# 328_data_collector.net
KiCad netlist of a schematic drawn in EAGLE
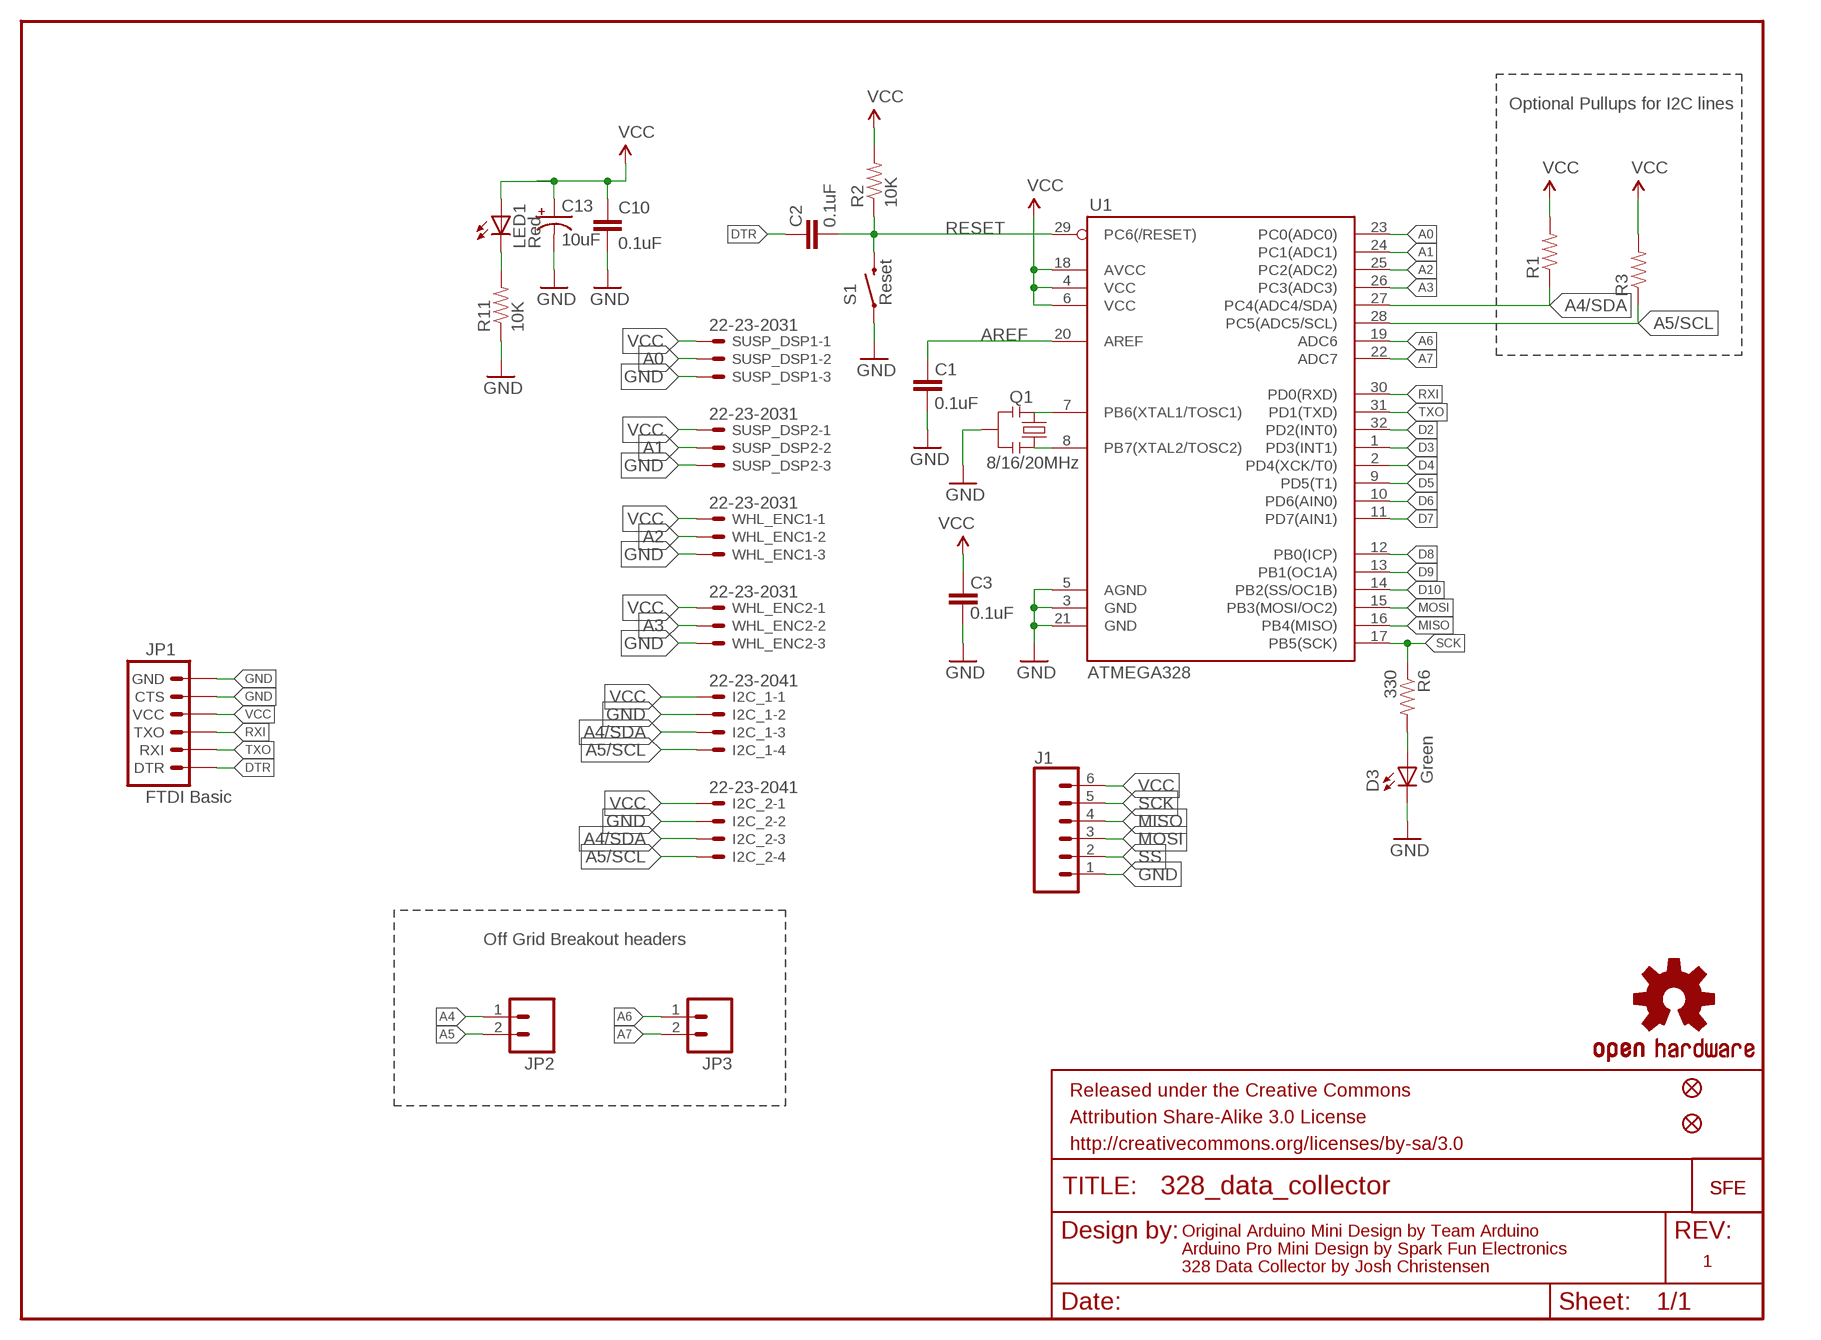
[diagram p0: schematic, sheet 1]

(export (version "E")
  (design (tool "Eeschema 10.0.6"))
  (components
    (comp (ref "C1")
      (value "0.1uF")
      (footprint "eagle-import:0603-CAP")
      (libsource (lib "eagle-import") (part "CAP0603-CAP"))
    )
    (comp (ref "C2")
      (value "0.1uF")
      (footprint "eagle-import:0603-CAP")
      (libsource (lib "eagle-import") (part "CAP0603-CAP"))
    )
    (comp (ref "C3")
      (value "0.1uF")
      (footprint "eagle-import:0603-CAP")
      (libsource (lib "eagle-import") (part "CAP0603-CAP"))
    )
    (comp (ref "C10")
      (value "0.1uF")
      (footprint "eagle-import:0603-CAP")
      (libsource (lib "eagle-import") (part "CAP0603-CAP"))
    )
    (comp (ref "C13")
      (value "10uF")
      (footprint "eagle-import:EIA3216")
      (libsource (lib "eagle-import") (part "CAP_POL1206"))
    )
    (comp (ref "D3")
      (value "Green")
      (footprint "eagle-import:0603-LED-ALT1")
      (libsource (lib "eagle-import") (part "LED"))
    )
    (comp (ref "FRAME1")
      (value "FRAME-LETTER")
      (footprint "eagle-import:CREATIVE_COMMONS")
      (libsource (lib "eagle-import") (part "FRAME-LETTER"))
    )
    (comp (ref "I2C_1")
      (value "22-23-2041")
      (footprint "eagle-import:22-23-2041")
      (fields (field (name "MF") "MOLEX"))
      (libsource (lib "eagle-import") (part "22-23-2041"))
    )
    (comp (ref "I2C_2")
      (value "22-23-2041")
      (footprint "eagle-import:22-23-2041")
      (fields (field (name "MF") "MOLEX"))
      (libsource (lib "eagle-import") (part "22-23-2041"))
    )
    (comp (ref "J1")
      (value "CONN_06SILK_FEMALE_PTH")
      (footprint "eagle-import:1X06")
      (libsource (lib "eagle-import") (part "CONN_06SILK_FEMALE_PTH"))
    )
    (comp (ref "JP1")
      (value "FTDI Basic")
      (footprint "eagle-import:1X06")
      (libsource (lib "eagle-import") (part "ARDUINO_SERIAL_PROGRAMPTH"))
    )
    (comp (ref "JP2")
      (value "M02PTH")
      (footprint "eagle-import:1X02")
      (libsource (lib "eagle-import") (part "M02PTH"))
    )
    (comp (ref "JP3")
      (value "M02PTH")
      (footprint "eagle-import:1X02")
      (libsource (lib "eagle-import") (part "M02PTH"))
    )
    (comp (ref "JP5")
      (value "FIDUCIALUFIDUCIAL")
      (footprint "eagle-import:MICRO-FIDUCIAL")
      (libsource (lib "eagle-import") (part "FIDUCIALUFIDUCIAL"))
    )
    (comp (ref "JP8")
      (value "FIDUCIALUFIDUCIAL")
      (footprint "eagle-import:MICRO-FIDUCIAL")
      (libsource (lib "eagle-import") (part "FIDUCIALUFIDUCIAL"))
    )
    (comp (ref "LED1")
      (value "Red")
      (footprint "eagle-import:0603-LED-ALT1")
      (libsource (lib "eagle-import") (part "LED"))
    )
    (comp (ref "Q1")
      (value "8/16/20MHz")
      (footprint "eagle-import:RESONATOR-SMD-1_1")
      (libsource (lib "eagle-import") (part "RESONATOR1{colon}1"))
    )
    (comp (ref "R1")
      (value "RESISTOR0603-RES")
      (footprint "eagle-import:0603-RES")
      (libsource (lib "eagle-import") (part "RESISTOR0603-RES"))
    )
    (comp (ref "R2")
      (value "10K")
      (footprint "eagle-import:0603-RES")
      (libsource (lib "eagle-import") (part "RESISTOR0603-RES"))
    )
    (comp (ref "R3")
      (value "RESISTOR0603-RES")
      (footprint "eagle-import:0603-RES")
      (libsource (lib "eagle-import") (part "RESISTOR0603-RES"))
    )
    (comp (ref "R6")
      (value "330")
      (footprint "eagle-import:0603-RES")
      (libsource (lib "eagle-import") (part "RESISTOR0603-RES"))
    )
    (comp (ref "R11")
      (value "10K")
      (footprint "eagle-import:0603-RES")
      (libsource (lib "eagle-import") (part "RESISTOR0603-RES"))
    )
    (comp (ref "S1")
      (value "Reset")
      (footprint "eagle-import:TACTILE-SWITCH-SMD-ALT01")
      (libsource (lib "eagle-import") (part "SWITCH-MOMENTARY-2SMD-ALT01"))
    )
    (comp (ref "SUSP_DSP1")
      (value "22-23-2031")
      (footprint "eagle-import:22-23-2031")
      (fields (field (name "MF") "MOLEX"))
      (libsource (lib "eagle-import") (part "22-23-2031"))
    )
    (comp (ref "SUSP_DSP2")
      (value "22-23-2031")
      (footprint "eagle-import:22-23-2031")
      (fields (field (name "MF") "MOLEX"))
      (libsource (lib "eagle-import") (part "22-23-2031"))
    )
    (comp (ref "U$1")
      (value "LOGO-SFESK")
      (footprint "eagle-import:SFE-LOGO-FLAME")
      (libsource (lib "eagle-import") (part "LOGO-SFESK"))
    )
    (comp (ref "U$3")
      (value "OSHW-LOGOS")
      (footprint "eagle-import:OSHW-LOGO-S")
      (libsource (lib "eagle-import") (part "OSHW-LOGOS"))
    )
    (comp (ref "U$11")
      (value "LOGO-SFENEW")
      (footprint "eagle-import:SFE-NEW-WEBLOGO")
      (libsource (lib "eagle-import") (part "LOGO-SFENEW"))
    )
    (comp (ref "U1")
      (value "ATMEGA328")
      (footprint "eagle-import:TQFP32-08")
      (libsource (lib "eagle-import") (part "ATMEGA168"))
    )
    (comp (ref "WHL_ENC1")
      (value "22-23-2031")
      (footprint "eagle-import:22-23-2031")
      (fields (field (name "MF") "MOLEX"))
      (libsource (lib "eagle-import") (part "22-23-2031"))
    )
    (comp (ref "WHL_ENC2")
      (value "22-23-2031")
      (footprint "eagle-import:22-23-2031")
      (fields (field (name "MF") "MOLEX"))
      (libsource (lib "eagle-import") (part "22-23-2031"))
    )
  )
  (nets
    (net (code "1") (name "/AREF") (class "Default")
      (node (ref "C1") (pin "2") (pinfunction "2_2") (pintype "passive"))
      (node (ref "U1") (pin "20") (pinfunction "AREF_20") (pintype "bidirectional"))
    )
    (net (code "2") (name "/RESET") (class "Default")
      (node (ref "C2") (pin "1") (pinfunction "1_1") (pintype "passive"))
      (node (ref "R2") (pin "1") (pinfunction "1_1") (pintype "passive"))
      (node (ref "S1") (pin "3") (pinfunction "2_3") (pintype "passive"))
      (node (ref "S1") (pin "4") (pinfunction "2_4") (pintype "passive"))
      (node (ref "U1") (pin "29") (pinfunction "PC6(/RESET)_29") (pintype "bidirectional"))
    )
    (net (code "3") (name "A0") (class "Default")
      (node (ref "SUSP_DSP1") (pin "2") (pinfunction "S_2") (pintype "passive"))
      (node (ref "U1") (pin "23") (pinfunction "PC0(ADC0)_23") (pintype "bidirectional"))
    )
    (net (code "4") (name "A1") (class "Default")
      (node (ref "SUSP_DSP2") (pin "2") (pinfunction "S_2") (pintype "passive"))
      (node (ref "U1") (pin "24") (pinfunction "PC1(ADC1)_24") (pintype "bidirectional"))
    )
    (net (code "5") (name "A2") (class "Default")
      (node (ref "U1") (pin "25") (pinfunction "PC2(ADC2)_25") (pintype "bidirectional"))
      (node (ref "WHL_ENC1") (pin "2") (pinfunction "S_2") (pintype "passive"))
    )
    (net (code "6") (name "A3") (class "Default")
      (node (ref "U1") (pin "26") (pinfunction "PC3(ADC3)_26") (pintype "bidirectional"))
      (node (ref "WHL_ENC2") (pin "2") (pinfunction "S_2") (pintype "passive"))
    )
    (net (code "7") (name "A4") (class "Default")
      (node (ref "JP2") (pin "1") (pinfunction "1_1") (pintype "passive"))
    )
    (net (code "8") (name "A4{slash}SDA") (class "Default")
      (node (ref "I2C_1") (pin "3") (pinfunction "S_3") (pintype "passive"))
      (node (ref "I2C_2") (pin "3") (pinfunction "S_3") (pintype "passive"))
      (node (ref "R1") (pin "1") (pinfunction "1_1") (pintype "passive"))
      (node (ref "U1") (pin "27") (pinfunction "PC4(ADC4/SDA)_27") (pintype "bidirectional"))
    )
    (net (code "9") (name "A5") (class "Default")
      (node (ref "JP2") (pin "2") (pinfunction "2_2") (pintype "passive"))
    )
    (net (code "10") (name "A5{slash}SCL") (class "Default")
      (node (ref "I2C_1") (pin "4") (pinfunction "S_4") (pintype "passive"))
      (node (ref "I2C_2") (pin "4") (pinfunction "S_4") (pintype "passive"))
      (node (ref "R3") (pin "1") (pinfunction "1_1") (pintype "passive"))
      (node (ref "U1") (pin "28") (pinfunction "PC5(ADC5/SCL)_28") (pintype "bidirectional"))
    )
    (net (code "11") (name "A6") (class "Default")
      (node (ref "JP3") (pin "1") (pinfunction "1_1") (pintype "passive"))
      (node (ref "U1") (pin "19") (pinfunction "ADC6_19") (pintype "bidirectional"))
    )
    (net (code "12") (name "A7") (class "Default")
      (node (ref "JP3") (pin "2") (pinfunction "2_2") (pintype "passive"))
      (node (ref "U1") (pin "22") (pinfunction "ADC7_22") (pintype "bidirectional"))
    )
    (net (code "13") (name "D2") (class "Default")
      (node (ref "U1") (pin "32") (pinfunction "PD2(INT0)_32") (pintype "bidirectional"))
    )
    (net (code "14") (name "D3") (class "Default")
      (node (ref "U1") (pin "1") (pinfunction "PD3(INT1)_1") (pintype "bidirectional"))
    )
    (net (code "15") (name "D4") (class "Default")
      (node (ref "U1") (pin "2") (pinfunction "PD4(XCK/T0)_2") (pintype "bidirectional"))
    )
    (net (code "16") (name "D5") (class "Default")
      (node (ref "U1") (pin "9") (pinfunction "PD5(T1)_9") (pintype "bidirectional"))
    )
    (net (code "17") (name "D6") (class "Default")
      (node (ref "U1") (pin "10") (pinfunction "PD6(AIN0)_10") (pintype "bidirectional"))
    )
    (net (code "18") (name "D7") (class "Default")
      (node (ref "U1") (pin "11") (pinfunction "PD7(AIN1)_11") (pintype "bidirectional"))
    )
    (net (code "19") (name "D8") (class "Default")
      (node (ref "U1") (pin "12") (pinfunction "PB0(ICP)_12") (pintype "bidirectional"))
    )
    (net (code "20") (name "D9") (class "Default")
      (node (ref "U1") (pin "13") (pinfunction "PB1(OC1A)_13") (pintype "bidirectional"))
    )
    (net (code "21") (name "D10") (class "Default")
      (node (ref "U1") (pin "14") (pinfunction "PB2(SS/OC1B)_14") (pintype "bidirectional"))
    )
    (net (code "22") (name "DTR") (class "Default")
      (node (ref "C2") (pin "2") (pinfunction "2_2") (pintype "passive"))
      (node (ref "JP1") (pin "1") (pinfunction "DTR_1") (pintype "passive"))
    )
    (net (code "23") (name "GND") (class "Default")
      (node (ref "C1") (pin "1") (pinfunction "1_1") (pintype "passive"))
      (node (ref "C10") (pin "2") (pinfunction "2_2") (pintype "passive"))
      (node (ref "C13") (pin "C") (pinfunction "-_C") (pintype "passive"))
      (node (ref "C3") (pin "1") (pinfunction "1_1") (pintype "passive"))
      (node (ref "D3") (pin "C") (pinfunction "C_C") (pintype "passive"))
      (node (ref "I2C_1") (pin "2") (pinfunction "S_2") (pintype "passive"))
      (node (ref "I2C_2") (pin "2") (pinfunction "S_2") (pintype "passive"))
      (node (ref "J1") (pin "1") (pinfunction "1_1") (pintype "passive"))
      (node (ref "JP1") (pin "5") (pinfunction "CTS_5") (pintype "passive"))
      (node (ref "JP1") (pin "6") (pinfunction "GND_6") (pintype "passive"))
      (node (ref "Q1") (pin "2") (pinfunction "2_2") (pintype "passive"))
      (node (ref "R11") (pin "1") (pinfunction "1_1") (pintype "passive"))
      (node (ref "S1") (pin "1") (pinfunction "1_1") (pintype "passive"))
      (node (ref "S1") (pin "2") (pinfunction "1_2") (pintype "passive"))
      (node (ref "SUSP_DSP1") (pin "3") (pinfunction "S_3") (pintype "passive"))
      (node (ref "SUSP_DSP2") (pin "3") (pinfunction "S_3") (pintype "passive"))
      (node (ref "U1") (pin "21") (pinfunction "GND_21") (pintype "bidirectional"))
      (node (ref "U1") (pin "3") (pinfunction "GND_3") (pintype "bidirectional"))
      (node (ref "U1") (pin "5") (pinfunction "AGND_5") (pintype "bidirectional"))
      (node (ref "WHL_ENC1") (pin "3") (pinfunction "S_3") (pintype "passive"))
      (node (ref "WHL_ENC2") (pin "3") (pinfunction "S_3") (pintype "passive"))
    )
    (net (code "24") (name "MISO") (class "Default")
      (node (ref "J1") (pin "4") (pinfunction "4_4") (pintype "passive"))
      (node (ref "U1") (pin "16") (pinfunction "PB4(MISO)_16") (pintype "bidirectional"))
    )
    (net (code "25") (name "MOSI") (class "Default")
      (node (ref "J1") (pin "3") (pinfunction "3_3") (pintype "passive"))
      (node (ref "U1") (pin "15") (pinfunction "PB3(MOSI/OC2)_15") (pintype "bidirectional"))
    )
    (net (code "26") (name "Net-(D3-PadA)") (class "Default")
      (node (ref "D3") (pin "A") (pinfunction "A_A") (pintype "passive"))
      (node (ref "R6") (pin "2") (pinfunction "2_2") (pintype "passive"))
    )
    (net (code "27") (name "Net-(LED1-PadC)") (class "Default")
      (node (ref "LED1") (pin "C") (pinfunction "C_C") (pintype "passive"))
      (node (ref "R11") (pin "2") (pinfunction "2_2") (pintype "passive"))
    )
    (net (code "28") (name "Net-(U1-PB6(XTAL1{slash}TOSC1))") (class "Default")
      (node (ref "Q1") (pin "1") (pinfunction "1_1") (pintype "passive"))
      (node (ref "U1") (pin "7") (pinfunction "PB6(XTAL1/TOSC1)_7") (pintype "bidirectional"))
    )
    (net (code "29") (name "Net-(U1-PB7(XTAL2{slash}TOSC2))") (class "Default")
      (node (ref "Q1") (pin "3") (pinfunction "3_3") (pintype "passive"))
      (node (ref "U1") (pin "8") (pinfunction "PB7(XTAL2/TOSC2)_8") (pintype "bidirectional"))
    )
    (net (code "30") (name "RXI") (class "Default")
      (node (ref "JP1") (pin "3") (pinfunction "TXO_3") (pintype "passive"))
      (node (ref "U1") (pin "30") (pinfunction "PD0(RXD)_30") (pintype "bidirectional"))
    )
    (net (code "31") (name "SCK") (class "Default")
      (node (ref "J1") (pin "5") (pinfunction "5_5") (pintype "passive"))
      (node (ref "R6") (pin "1") (pinfunction "1_1") (pintype "passive"))
      (node (ref "U1") (pin "17") (pinfunction "PB5(SCK)_17") (pintype "bidirectional"))
    )
    (net (code "32") (name "SS") (class "Default")
      (node (ref "J1") (pin "2") (pinfunction "2_2") (pintype "passive"))
    )
    (net (code "33") (name "TXO") (class "Default")
      (node (ref "JP1") (pin "2") (pinfunction "RXI_2") (pintype "passive"))
      (node (ref "U1") (pin "31") (pinfunction "PD1(TXD)_31") (pintype "bidirectional"))
    )
    (net (code "34") (name "VCC") (class "Default")
      (node (ref "C10") (pin "1") (pinfunction "1_1") (pintype "passive"))
      (node (ref "C13") (pin "A") (pinfunction "+_A") (pintype "passive"))
      (node (ref "C3") (pin "2") (pinfunction "2_2") (pintype "passive"))
      (node (ref "I2C_1") (pin "1") (pinfunction "S_1") (pintype "passive"))
      (node (ref "I2C_2") (pin "1") (pinfunction "S_1") (pintype "passive"))
      (node (ref "J1") (pin "6") (pinfunction "6_6") (pintype "passive"))
      (node (ref "JP1") (pin "4") (pinfunction "VCC_4") (pintype "passive"))
      (node (ref "LED1") (pin "A") (pinfunction "A_A") (pintype "passive"))
      (node (ref "R1") (pin "2") (pinfunction "2_2") (pintype "passive"))
      (node (ref "R2") (pin "2") (pinfunction "2_2") (pintype "passive"))
      (node (ref "R3") (pin "2") (pinfunction "2_2") (pintype "passive"))
      (node (ref "SUSP_DSP1") (pin "1") (pinfunction "S_1") (pintype "passive"))
      (node (ref "SUSP_DSP2") (pin "1") (pinfunction "S_1") (pintype "passive"))
      (node (ref "U1") (pin "18") (pinfunction "AVCC_18") (pintype "bidirectional"))
      (node (ref "U1") (pin "4") (pinfunction "VCC_4") (pintype "bidirectional"))
      (node (ref "U1") (pin "6") (pinfunction "VCC_6") (pintype "bidirectional"))
      (node (ref "WHL_ENC1") (pin "1") (pinfunction "S_1") (pintype "passive"))
      (node (ref "WHL_ENC2") (pin "1") (pinfunction "S_1") (pintype "passive"))
    )
  )
)
